# CapTouchKeyboard_v2_0.net
KiCad netlist of a schematic drawn in Altium Designer
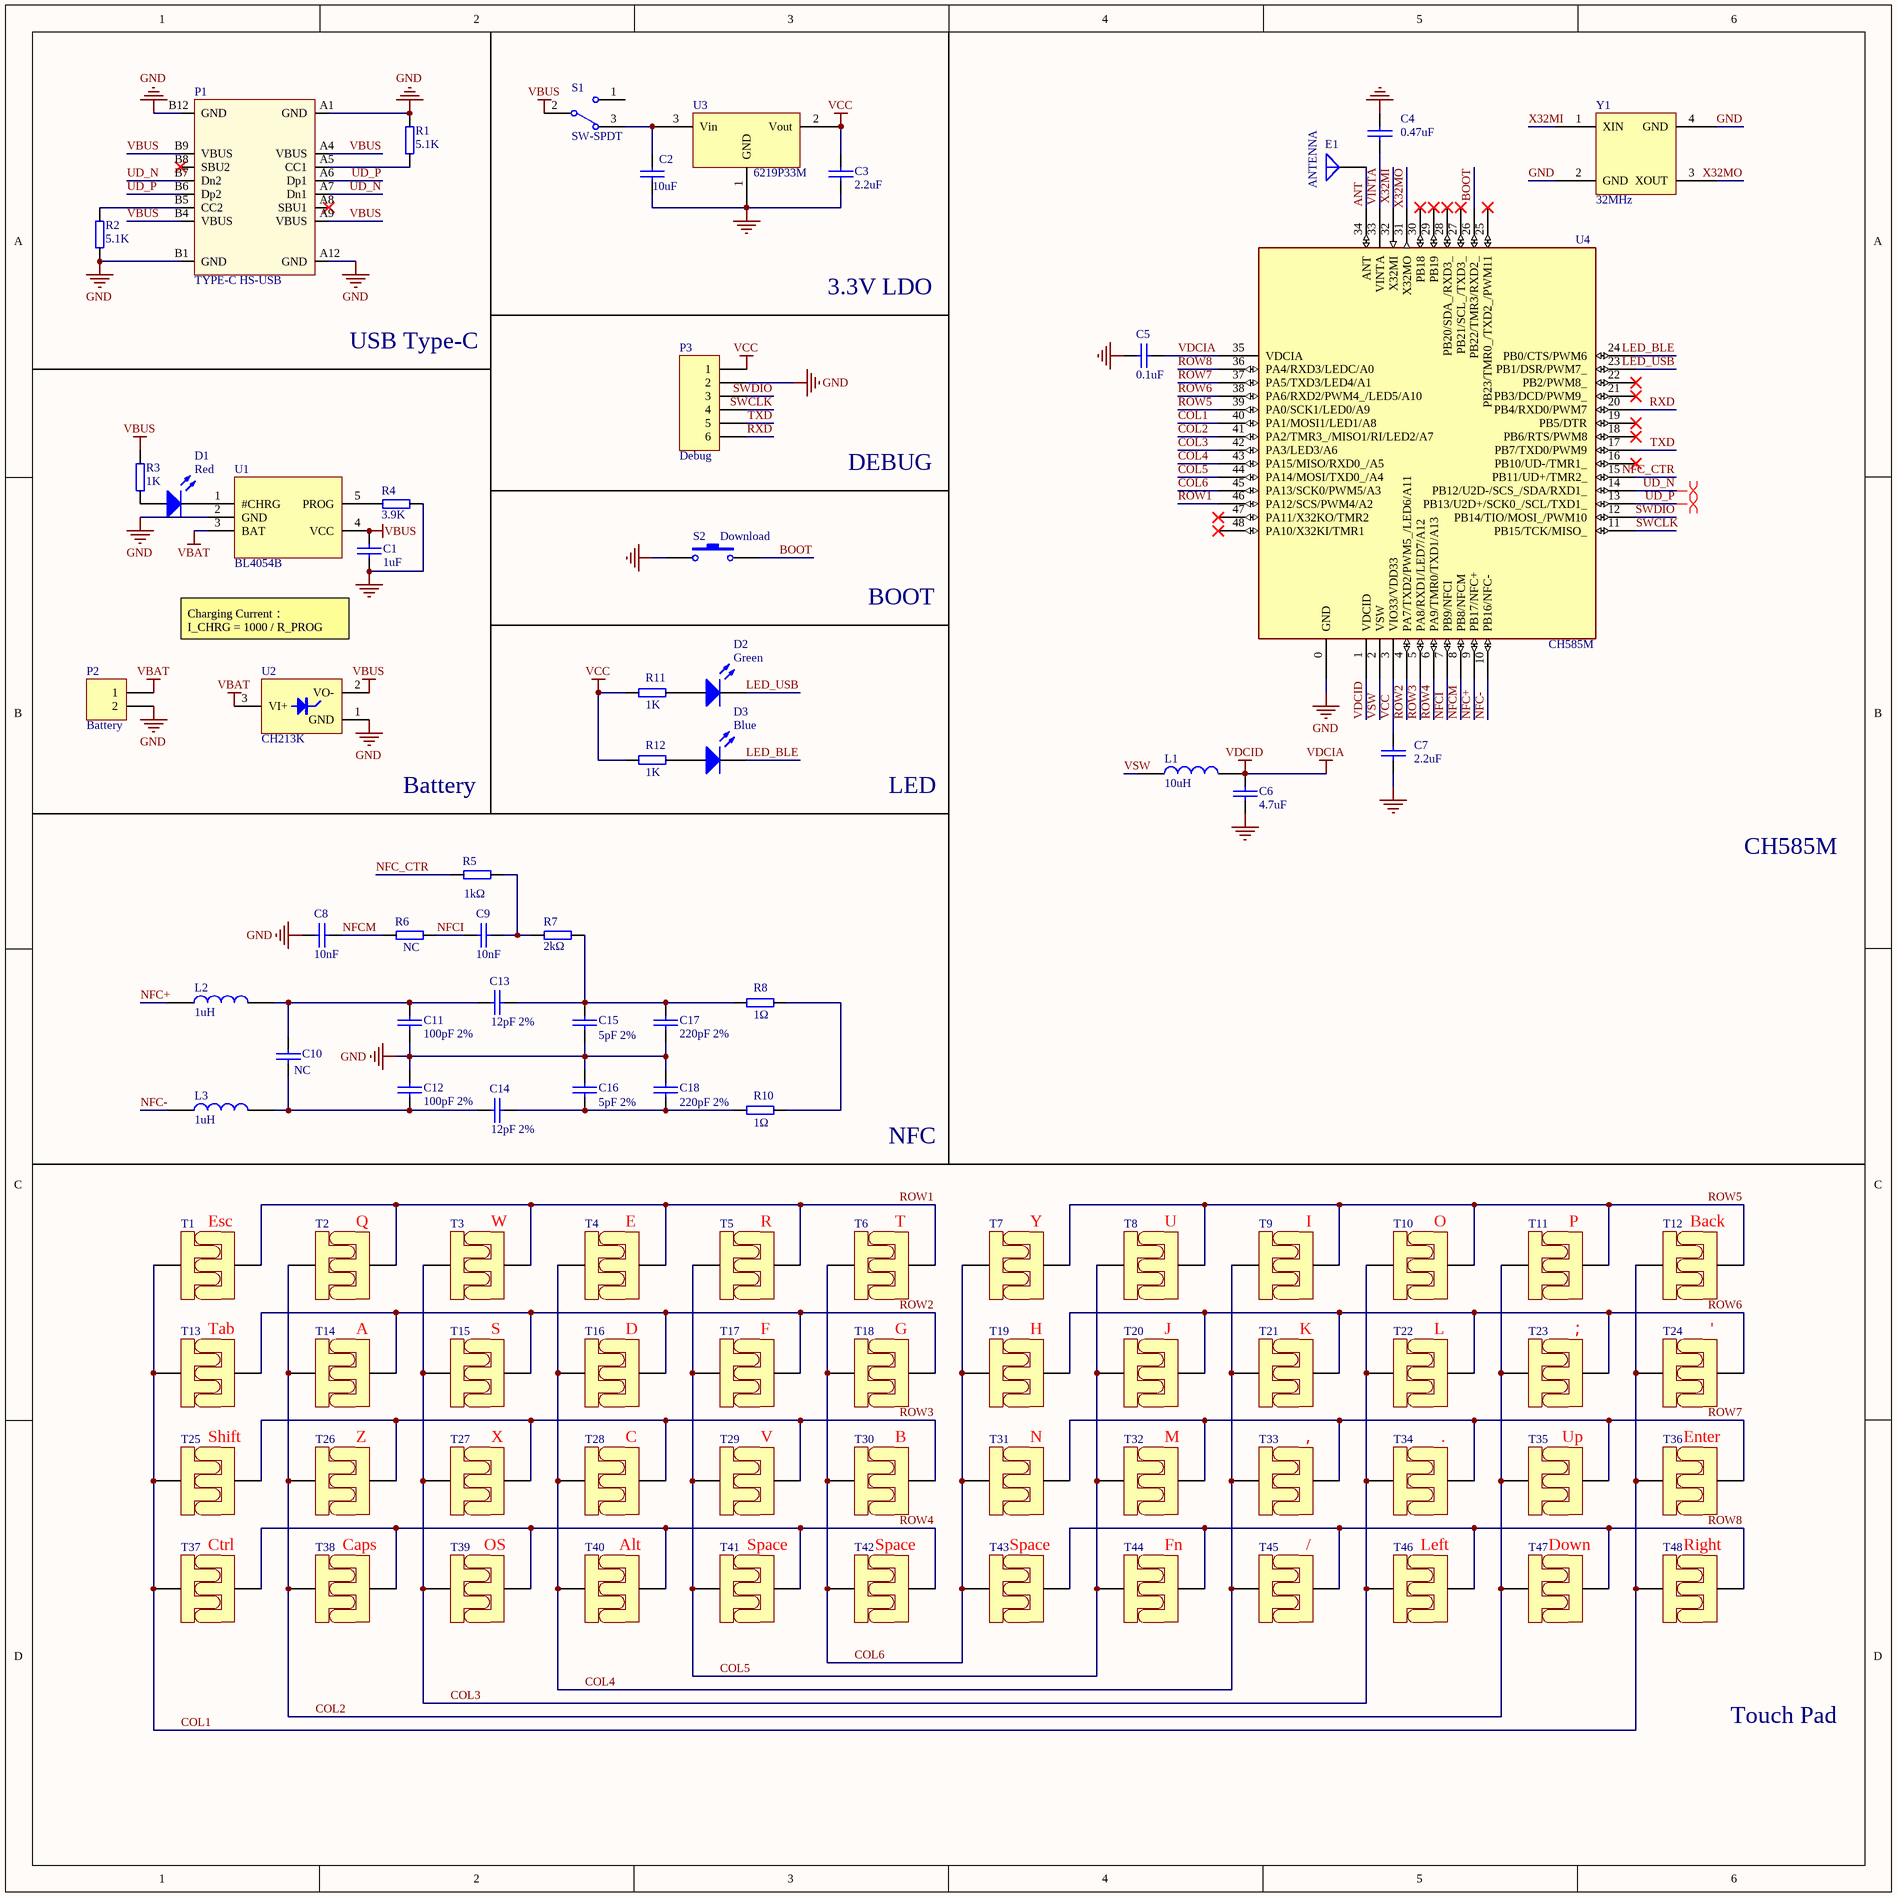
[diagram p0: CapTouchKeyboard_v2.0.SchDoc]

(export (version "E")
  (design (tool "Eeschema 10.0.6"))
  (components
    (comp (ref "C1")
      (value "1uF")
      (footprint "CapTouchKeyboard:0402_C")
      (description "Capacitor")
      (libsource (lib "*") (part "CAP"))
    )
    (comp (ref "C2")
      (value "10uF")
      (footprint "CapTouchKeyboard:0603_C")
      (description "Capacitor")
      (libsource (lib "*") (part "CAP"))
    )
    (comp (ref "C3")
      (value "2.2uF")
      (footprint "CapTouchKeyboard:0402_C")
      (description "Capacitor")
      (libsource (lib "*") (part "CAP"))
    )
    (comp (ref "C4")
      (value "0.47uF")
      (footprint "CapTouchKeyboard:0402_C")
      (description "Capacitor")
      (libsource (lib "*") (part "CAP"))
    )
    (comp (ref "C5")
      (value "0.1uF")
      (footprint "CapTouchKeyboard:0402_C")
      (description "Capacitor")
      (libsource (lib "*") (part "CAP"))
    )
    (comp (ref "C6")
      (value "4.7uF")
      (footprint "CapTouchKeyboard:0402_C")
      (description "Capacitor")
      (libsource (lib "") (part "CAP_1"))
    )
    (comp (ref "C7")
      (value "2.2uF")
      (footprint "CapTouchKeyboard:0402_C")
      (description "Capacitor")
      (libsource (lib "*") (part "CAP"))
    )
    (comp (ref "C8")
      (value "10nF")
      (footprint "CapTouchKeyboard:0402_C")
      (description "Capacitor")
      (libsource (lib "wch_sch_others") (part "CAP"))
    )
    (comp (ref "C9")
      (value "10nF")
      (footprint "CapTouchKeyboard:0402_C")
      (description "Capacitor")
      (libsource (lib "wch_sch_others") (part "CAP"))
    )
    (comp (ref "C10")
      (value "NC")
      (footprint "CapTouchKeyboard:0402_C")
      (description "Capacitor")
      (libsource (lib "wch_sch_others") (part "CAP"))
    )
    (comp (ref "C11")
      (value "100pF 2%")
      (footprint "CapTouchKeyboard:0402_C")
      (description "Capacitor")
      (libsource (lib "wch_sch_others") (part "CAP"))
    )
    (comp (ref "C12")
      (value "100pF 2%")
      (footprint "CapTouchKeyboard:0402_C")
      (description "Capacitor")
      (libsource (lib "wch_sch_others") (part "CAP"))
    )
    (comp (ref "C13")
      (value "12pF 2%")
      (footprint "CapTouchKeyboard:0402_C")
      (description "Capacitor")
      (libsource (lib "wch_sch_others") (part "CAP"))
    )
    (comp (ref "C14")
      (value "12pF 2%")
      (footprint "CapTouchKeyboard:0402_C")
      (description "Capacitor")
      (libsource (lib "wch_sch_others") (part "CAP"))
    )
    (comp (ref "C15")
      (value "5pF 2%")
      (footprint "CapTouchKeyboard:0402_C")
      (description "Capacitor")
      (libsource (lib "wch_sch_others") (part "CAP"))
    )
    (comp (ref "C16")
      (value "5pF 2%")
      (footprint "CapTouchKeyboard:0402_C")
      (description "Capacitor")
      (libsource (lib "wch_sch_others") (part "CAP"))
    )
    (comp (ref "C17")
      (value "220pF 2%")
      (footprint "CapTouchKeyboard:0402_C")
      (description "Capacitor")
      (libsource (lib "wch_sch_others") (part "CAP"))
    )
    (comp (ref "C18")
      (value "220pF 2%")
      (footprint "CapTouchKeyboard:0402_C")
      (description "Capacitor")
      (libsource (lib "wch_sch_others") (part "CAP"))
    )
    (comp (ref "D1")
      (value "Red")
      (footprint "ADLIB:0603+")
      (description "Typical INFRARED GaAs LED")
      (fields (field (name "PUBLISHER") "Altium Limited"))
      (libsource (lib "Miscellaneous Devices") (part "LED0"))
    )
    (comp (ref "D2")
      (value "Green")
      (footprint "ADLIB:0603+")
      (description "Typical INFRARED GaAs LED")
      (fields (field (name "PUBLISHER") "Altium Limited"))
      (libsource (lib "Miscellaneous Devices") (part "LED0"))
    )
    (comp (ref "D3")
      (value "Blue")
      (footprint "ADLIB:0603+")
      (description "Typical INFRARED GaAs LED")
      (fields (field (name "PUBLISHER") "Altium Limited"))
      (libsource (lib "Miscellaneous Devices") (part "LED0"))
    )
    (comp (ref "E1")
      (value "ANTENNA")
      (footprint "CapTouchKeyboard:ANT-F-1-2.4G-0.8mmFR4-WCH")
      (description "Generic Antenna")
      (libsource (lib "*") (part "ANTENNA"))
    )
    (comp (ref "L1")
      (value "10uH")
      (footprint "CapTouchKeyboard:SMD_2x2mm")
      (libsource (lib "*") (part "INDUCTOR"))
    )
    (comp (ref "L2") (value "1uH") (footprint "CHXXX:0603") (libsource (lib "*") (part "INDUCTOR")))
    (comp (ref "L3") (value "1uH") (footprint "CHXXX:0603") (libsource (lib "*") (part "INDUCTOR")))
    (comp (ref "P1")
      (value "TYPE-C HS-USB")
      (footprint "USB_TYPE_C_DS_2")
      (description "Type-C USB2.0 母座")
      (libsource (lib "CapTouchKeyboard") (part "TYPE-C-Receptacle-2.0"))
    )
    (comp (ref "P2")
      (value "Battery")
      (footprint "CapTouchKeyboard:XH-2P-P1.25mm-WT")
      (description "Header, 2-Pin")
      (libsource (lib "wch_sch_others") (part "HEADER 2"))
    )
    (comp (ref "P3")
      (value "Debug")
      (footprint "CapTouchKeyboard:HDR1X6H")
      (description "Header, 6-Pin")
      (libsource (lib "CapTouchKeyboard") (part "HEADER 6"))
    )
    (comp (ref "R1") (value "5.1K") (footprint "CHXXX:0402") (libsource (lib "wch_sch_others") (part "RES")))
    (comp (ref "R2") (value "5.1K") (footprint "CHXXX:0402") (libsource (lib "wch_sch_others") (part "RES")))
    (comp (ref "R3") (value "1K") (footprint "CHXXX:0402") (libsource (lib "wch_sch_others") (part "RES")))
    (comp (ref "R4") (value "3.9K") (footprint "CHXXX:0402") (libsource (lib "wch_sch_others") (part "RES")))
    (comp (ref "R5") (value "1kΩ") (footprint "CHXXX:0402") (libsource (lib "wch_sch_others") (part "RES")))
    (comp (ref "R6") (value "NC") (footprint "CHXXX:0402") (libsource (lib "wch_sch_others") (part "RES")))
    (comp (ref "R7") (value "2kΩ") (footprint "CHXXX:0402") (libsource (lib "wch_sch_others") (part "RES")))
    (comp (ref "R8") (value "1Ω") (footprint "CHXXX:0402") (libsource (lib "wch_sch_others") (part "RES")))
    (comp (ref "R10") (value "1Ω") (footprint "CHXXX:0402") (libsource (lib "wch_sch_others") (part "RES")))
    (comp (ref "R11") (value "1K") (footprint "CHXXX:0402") (libsource (lib "wch_sch_others") (part "RES")))
    (comp (ref "R12") (value "1K") (footprint "CHXXX:0402") (libsource (lib "wch_sch_others") (part "RES")))
    (comp (ref "S1")
      (value "SW-SPDT")
      (footprint "CapTouchKeyboard:SW1 - SMD (2)")
      (description "SPDT Subminiature Toggle Switch, Right Angle Mounting, Vertical Actuation")
      (fields (field (name "PUBLISHER") "Altium Limited"))
      (libsource (lib "Miscellaneous Devices") (part "SW-SPDT"))
    )
    (comp (ref "S2")
      (value "Download")
      (footprint "CapTouchKeyboard:SMD_4.1x2.3x3.5mm-KEY (2)")
      (description "Switch")
      (fields (field (name "PUBLISHER") "Altium Limited"))
      (libsource (lib "CapTouchKeyboard") (part "SW-PB"))
    )
    (comp (ref "T1")
      (value "TouchPad")
      (footprint "CapTouchKeyboard:TOUCH_PAD")
      (libsource (lib "CapTouchKeyboard") (part "TouchPad"))
    )
    (comp (ref "T2")
      (value "TouchPad")
      (footprint "CapTouchKeyboard:TOUCH_PAD")
      (libsource (lib "CapTouchKeyboard") (part "TouchPad"))
    )
    (comp (ref "T3")
      (value "TouchPad")
      (footprint "CapTouchKeyboard:TOUCH_PAD")
      (libsource (lib "CapTouchKeyboard") (part "TouchPad"))
    )
    (comp (ref "T4")
      (value "TouchPad")
      (footprint "CapTouchKeyboard:TOUCH_PAD")
      (libsource (lib "CapTouchKeyboard") (part "TouchPad"))
    )
    (comp (ref "T5")
      (value "TouchPad")
      (footprint "CapTouchKeyboard:TOUCH_PAD")
      (libsource (lib "CapTouchKeyboard") (part "TouchPad"))
    )
    (comp (ref "T6")
      (value "TouchPad")
      (footprint "CapTouchKeyboard:TOUCH_PAD")
      (libsource (lib "CapTouchKeyboard") (part "TouchPad"))
    )
    (comp (ref "T7")
      (value "TouchPad")
      (footprint "CapTouchKeyboard:TOUCH_PAD")
      (libsource (lib "CapTouchKeyboard") (part "TouchPad"))
    )
    (comp (ref "T8")
      (value "TouchPad")
      (footprint "CapTouchKeyboard:TOUCH_PAD")
      (libsource (lib "CapTouchKeyboard") (part "TouchPad"))
    )
    (comp (ref "T9")
      (value "TouchPad")
      (footprint "CapTouchKeyboard:TOUCH_PAD")
      (libsource (lib "CapTouchKeyboard") (part "TouchPad"))
    )
    (comp (ref "T10")
      (value "TouchPad")
      (footprint "CapTouchKeyboard:TOUCH_PAD")
      (libsource (lib "CapTouchKeyboard") (part "TouchPad"))
    )
    (comp (ref "T11")
      (value "TouchPad")
      (footprint "CapTouchKeyboard:TOUCH_PAD")
      (libsource (lib "CapTouchKeyboard") (part "TouchPad"))
    )
    (comp (ref "T12")
      (value "TouchPad")
      (footprint "CapTouchKeyboard:TOUCH_PAD")
      (libsource (lib "CapTouchKeyboard") (part "TouchPad"))
    )
    (comp (ref "T13")
      (value "TouchPad")
      (footprint "CapTouchKeyboard:TOUCH_PAD")
      (libsource (lib "CapTouchKeyboard") (part "TouchPad"))
    )
    (comp (ref "T14")
      (value "TouchPad")
      (footprint "CapTouchKeyboard:TOUCH_PAD")
      (libsource (lib "CapTouchKeyboard") (part "TouchPad"))
    )
    (comp (ref "T15")
      (value "TouchPad")
      (footprint "CapTouchKeyboard:TOUCH_PAD")
      (libsource (lib "CapTouchKeyboard") (part "TouchPad"))
    )
    (comp (ref "T16")
      (value "TouchPad")
      (footprint "CapTouchKeyboard:TOUCH_PAD")
      (libsource (lib "CapTouchKeyboard") (part "TouchPad"))
    )
    (comp (ref "T17")
      (value "TouchPad")
      (footprint "CapTouchKeyboard:TOUCH_PAD")
      (libsource (lib "CapTouchKeyboard") (part "TouchPad"))
    )
    (comp (ref "T18")
      (value "TouchPad")
      (footprint "CapTouchKeyboard:TOUCH_PAD")
      (libsource (lib "CapTouchKeyboard") (part "TouchPad"))
    )
    (comp (ref "T19")
      (value "TouchPad")
      (footprint "CapTouchKeyboard:TOUCH_PAD")
      (libsource (lib "CapTouchKeyboard") (part "TouchPad"))
    )
    (comp (ref "T20")
      (value "TouchPad")
      (footprint "CapTouchKeyboard:TOUCH_PAD")
      (libsource (lib "CapTouchKeyboard") (part "TouchPad"))
    )
    (comp (ref "T21")
      (value "TouchPad")
      (footprint "CapTouchKeyboard:TOUCH_PAD")
      (libsource (lib "CapTouchKeyboard") (part "TouchPad"))
    )
    (comp (ref "T22")
      (value "TouchPad")
      (footprint "CapTouchKeyboard:TOUCH_PAD")
      (libsource (lib "CapTouchKeyboard") (part "TouchPad"))
    )
    (comp (ref "T23")
      (value "TouchPad")
      (footprint "CapTouchKeyboard:TOUCH_PAD")
      (libsource (lib "CapTouchKeyboard") (part "TouchPad"))
    )
    (comp (ref "T24")
      (value "TouchPad")
      (footprint "CapTouchKeyboard:TOUCH_PAD")
      (libsource (lib "CapTouchKeyboard") (part "TouchPad"))
    )
    (comp (ref "T25")
      (value "TouchPad")
      (footprint "CapTouchKeyboard:TOUCH_PAD")
      (libsource (lib "CapTouchKeyboard") (part "TouchPad"))
    )
    (comp (ref "T26")
      (value "TouchPad")
      (footprint "CapTouchKeyboard:TOUCH_PAD")
      (libsource (lib "CapTouchKeyboard") (part "TouchPad"))
    )
    (comp (ref "T27")
      (value "TouchPad")
      (footprint "CapTouchKeyboard:TOUCH_PAD")
      (libsource (lib "CapTouchKeyboard") (part "TouchPad"))
    )
    (comp (ref "T28")
      (value "TouchPad")
      (footprint "CapTouchKeyboard:TOUCH_PAD")
      (libsource (lib "CapTouchKeyboard") (part "TouchPad"))
    )
    (comp (ref "T29")
      (value "TouchPad")
      (footprint "CapTouchKeyboard:TOUCH_PAD")
      (libsource (lib "CapTouchKeyboard") (part "TouchPad"))
    )
    (comp (ref "T30")
      (value "TouchPad")
      (footprint "CapTouchKeyboard:TOUCH_PAD")
      (libsource (lib "CapTouchKeyboard") (part "TouchPad"))
    )
    (comp (ref "T31")
      (value "TouchPad")
      (footprint "CapTouchKeyboard:TOUCH_PAD")
      (libsource (lib "CapTouchKeyboard") (part "TouchPad"))
    )
    (comp (ref "T32")
      (value "TouchPad")
      (footprint "CapTouchKeyboard:TOUCH_PAD")
      (libsource (lib "CapTouchKeyboard") (part "TouchPad"))
    )
    (comp (ref "T33")
      (value "TouchPad")
      (footprint "CapTouchKeyboard:TOUCH_PAD")
      (libsource (lib "CapTouchKeyboard") (part "TouchPad"))
    )
    (comp (ref "T34")
      (value "TouchPad")
      (footprint "CapTouchKeyboard:TOUCH_PAD")
      (libsource (lib "CapTouchKeyboard") (part "TouchPad"))
    )
    (comp (ref "T35")
      (value "TouchPad")
      (footprint "CapTouchKeyboard:TOUCH_PAD")
      (libsource (lib "CapTouchKeyboard") (part "TouchPad"))
    )
    (comp (ref "T36")
      (value "TouchPad")
      (footprint "CapTouchKeyboard:TOUCH_PAD")
      (libsource (lib "CapTouchKeyboard") (part "TouchPad"))
    )
    (comp (ref "T37")
      (value "TouchPad")
      (footprint "CapTouchKeyboard:TOUCH_PAD")
      (libsource (lib "CapTouchKeyboard") (part "TouchPad"))
    )
    (comp (ref "T38")
      (value "TouchPad")
      (footprint "CapTouchKeyboard:TOUCH_PAD")
      (libsource (lib "CapTouchKeyboard") (part "TouchPad"))
    )
    (comp (ref "T39")
      (value "TouchPad")
      (footprint "CapTouchKeyboard:TOUCH_PAD")
      (libsource (lib "CapTouchKeyboard") (part "TouchPad"))
    )
    (comp (ref "T40")
      (value "TouchPad")
      (footprint "CapTouchKeyboard:TOUCH_PAD")
      (libsource (lib "CapTouchKeyboard") (part "TouchPad"))
    )
    (comp (ref "T41")
      (value "TouchPad")
      (footprint "CapTouchKeyboard:TOUCH_PAD")
      (libsource (lib "CapTouchKeyboard") (part "TouchPad"))
    )
    (comp (ref "T42")
      (value "TouchPad")
      (footprint "CapTouchKeyboard:TOUCH_PAD")
      (libsource (lib "CapTouchKeyboard") (part "TouchPad"))
    )
    (comp (ref "T43")
      (value "TouchPad")
      (footprint "CapTouchKeyboard:TOUCH_PAD")
      (libsource (lib "CapTouchKeyboard") (part "TouchPad"))
    )
    (comp (ref "T44")
      (value "TouchPad")
      (footprint "CapTouchKeyboard:TOUCH_PAD")
      (libsource (lib "CapTouchKeyboard") (part "TouchPad"))
    )
    (comp (ref "T45")
      (value "TouchPad")
      (footprint "CapTouchKeyboard:TOUCH_PAD")
      (libsource (lib "CapTouchKeyboard") (part "TouchPad"))
    )
    (comp (ref "T46")
      (value "TouchPad")
      (footprint "CapTouchKeyboard:TOUCH_PAD")
      (libsource (lib "CapTouchKeyboard") (part "TouchPad"))
    )
    (comp (ref "T47")
      (value "TouchPad")
      (footprint "CapTouchKeyboard:TOUCH_PAD")
      (libsource (lib "CapTouchKeyboard") (part "TouchPad"))
    )
    (comp (ref "T48")
      (value "TouchPad")
      (footprint "CapTouchKeyboard:TOUCH_PAD")
      (libsource (lib "CapTouchKeyboard") (part "TouchPad"))
    )
    (comp (ref "U1")
      (value "BL4054B")
      (footprint "CHXXX:SOT-23-5")
      (description "具有热调节功能的800mA独立线性锂离子电池充电器")
      (libsource (lib "CapTouchKeyboard") (part "BL4054B"))
    )
    (comp (ref "U2")
      (value "CH213K")
      (footprint "CHXXX:SOT-23-3")
      (description "Ideal Diode 5V*1A")
      (libsource (lib "DHXXXSCH") (part "CH213K"))
    )
    (comp (ref "U3")
      (value "6219P33M")
      (footprint "CHXXX:SOT-23")
      (libsource (lib "wch_sch_others") (part "6219P33M"))
    )
    (comp (ref "U4")
      (value "CH585M")
      (footprint "QFN48_5X5")
      (description "RISC-V MCU with BLE/HSUSB/USB/NFC/ADC/PWM/2*SPI/I2C/4*UART/LCD")
      (libsource (lib "CapTouchKeyboard") (part "CH585M"))
    )
    (comp (ref "Y1")
      (value "32MHz")
      (footprint "CapTouchKeyboard:2016")
      (libsource (lib "wch_sch_others") (part "晶体"))
    )
  )
  (nets
    (net (code "1") (name "/ANT") (class "Default")
      (node (ref "E1") (pin "1") (pinfunction "A_1") (pintype "passive"))
      (node (ref "U4") (pin "34") (pinfunction "ANT_34") (pintype "bidirectional"))
    )
    (net (code "2") (name "/BOOT") (class "Default")
      (node (ref "S2") (pin "2") (pinfunction "2_2") (pintype "passive"))
      (node (ref "U4") (pin "26") (pinfunction "PB22/TMR3/RXD2__26") (pintype "bidirectional"))
    )
    (net (code "3") (name "/COL1") (class "Default")
      (node (ref "T1") (pin "1") (pinfunction "1_1") (pintype "passive"))
      (node (ref "T12") (pin "1") (pinfunction "1_1") (pintype "passive"))
      (node (ref "T13") (pin "1") (pinfunction "1_1") (pintype "passive"))
      (node (ref "T24") (pin "1") (pinfunction "1_1") (pintype "passive"))
      (node (ref "T25") (pin "1") (pinfunction "1_1") (pintype "passive"))
      (node (ref "T36") (pin "1") (pinfunction "1_1") (pintype "passive"))
      (node (ref "T37") (pin "1") (pinfunction "1_1") (pintype "passive"))
      (node (ref "T48") (pin "1") (pinfunction "1_1") (pintype "passive"))
      (node (ref "U4") (pin "40") (pinfunction "PA1/MOSI1/LED1/A8_40") (pintype "bidirectional"))
    )
    (net (code "4") (name "/COL2") (class "Default")
      (node (ref "T11") (pin "1") (pinfunction "1_1") (pintype "passive"))
      (node (ref "T14") (pin "1") (pinfunction "1_1") (pintype "passive"))
      (node (ref "T2") (pin "1") (pinfunction "1_1") (pintype "passive"))
      (node (ref "T23") (pin "1") (pinfunction "1_1") (pintype "passive"))
      (node (ref "T26") (pin "1") (pinfunction "1_1") (pintype "passive"))
      (node (ref "T35") (pin "1") (pinfunction "1_1") (pintype "passive"))
      (node (ref "T38") (pin "1") (pinfunction "1_1") (pintype "passive"))
      (node (ref "T47") (pin "1") (pinfunction "1_1") (pintype "passive"))
      (node (ref "U4") (pin "41") (pinfunction "PA2/TMR3_/MISO1/RI/LED2/A7_41") (pintype "bidirectional"))
    )
    (net (code "5") (name "/COL3") (class "Default")
      (node (ref "T10") (pin "1") (pinfunction "1_1") (pintype "passive"))
      (node (ref "T15") (pin "1") (pinfunction "1_1") (pintype "passive"))
      (node (ref "T22") (pin "1") (pinfunction "1_1") (pintype "passive"))
      (node (ref "T27") (pin "1") (pinfunction "1_1") (pintype "passive"))
      (node (ref "T3") (pin "1") (pinfunction "1_1") (pintype "passive"))
      (node (ref "T34") (pin "1") (pinfunction "1_1") (pintype "passive"))
      (node (ref "T39") (pin "1") (pinfunction "1_1") (pintype "passive"))
      (node (ref "T46") (pin "1") (pinfunction "1_1") (pintype "passive"))
      (node (ref "U4") (pin "42") (pinfunction "PA3/LED3/A6_42") (pintype "bidirectional"))
    )
    (net (code "6") (name "/COL4") (class "Default")
      (node (ref "T16") (pin "1") (pinfunction "1_1") (pintype "passive"))
      (node (ref "T21") (pin "1") (pinfunction "1_1") (pintype "passive"))
      (node (ref "T28") (pin "1") (pinfunction "1_1") (pintype "passive"))
      (node (ref "T33") (pin "1") (pinfunction "1_1") (pintype "passive"))
      (node (ref "T4") (pin "1") (pinfunction "1_1") (pintype "passive"))
      (node (ref "T40") (pin "1") (pinfunction "1_1") (pintype "passive"))
      (node (ref "T45") (pin "1") (pinfunction "1_1") (pintype "passive"))
      (node (ref "T9") (pin "1") (pinfunction "1_1") (pintype "passive"))
      (node (ref "U4") (pin "43") (pinfunction "PA15/MISO/RXD0_/A5_43") (pintype "bidirectional"))
    )
    (net (code "7") (name "/COL5") (class "Default")
      (node (ref "T17") (pin "1") (pinfunction "1_1") (pintype "passive"))
      (node (ref "T20") (pin "1") (pinfunction "1_1") (pintype "passive"))
      (node (ref "T29") (pin "1") (pinfunction "1_1") (pintype "passive"))
      (node (ref "T32") (pin "1") (pinfunction "1_1") (pintype "passive"))
      (node (ref "T41") (pin "1") (pinfunction "1_1") (pintype "passive"))
      (node (ref "T44") (pin "1") (pinfunction "1_1") (pintype "passive"))
      (node (ref "T5") (pin "1") (pinfunction "1_1") (pintype "passive"))
      (node (ref "T8") (pin "1") (pinfunction "1_1") (pintype "passive"))
      (node (ref "U4") (pin "44") (pinfunction "PA14/MOSI/TXD0_/A4_44") (pintype "bidirectional"))
    )
    (net (code "8") (name "/COL6") (class "Default")
      (node (ref "T18") (pin "1") (pinfunction "1_1") (pintype "passive"))
      (node (ref "T19") (pin "1") (pinfunction "1_1") (pintype "passive"))
      (node (ref "T30") (pin "1") (pinfunction "1_1") (pintype "passive"))
      (node (ref "T31") (pin "1") (pinfunction "1_1") (pintype "passive"))
      (node (ref "T42") (pin "1") (pinfunction "1_1") (pintype "passive"))
      (node (ref "T43") (pin "1") (pinfunction "1_1") (pintype "passive"))
      (node (ref "T6") (pin "1") (pinfunction "1_1") (pintype "passive"))
      (node (ref "T7") (pin "1") (pinfunction "1_1") (pintype "passive"))
      (node (ref "U4") (pin "45") (pinfunction "PA13/SCK0/PWM5/A3_45") (pintype "bidirectional"))
    )
    (net (code "9") (name "/LED_BLE") (class "Default")
      (node (ref "D3") (pin "2") (pinfunction "K_2") (pintype "passive"))
      (node (ref "U4") (pin "24") (pinfunction "PB0/CTS/PWM6_24") (pintype "bidirectional"))
    )
    (net (code "10") (name "/LED_USB") (class "Default")
      (node (ref "D2") (pin "2") (pinfunction "K_2") (pintype "passive"))
      (node (ref "U4") (pin "23") (pinfunction "PB1/DSR/PWM7__23") (pintype "bidirectional"))
    )
    (net (code "11") (name "/NFC+") (class "Default")
      (node (ref "L2") (pin "1") (pinfunction "1_1") (pintype "passive"))
      (node (ref "U4") (pin "9") (pinfunction "PB17/NFC+_9") (pintype "bidirectional"))
    )
    (net (code "12") (name "/NFC-") (class "Default")
      (node (ref "L3") (pin "1") (pinfunction "1_1") (pintype "passive"))
      (node (ref "U4") (pin "10") (pinfunction "PB16/NFC-_10") (pintype "bidirectional"))
    )
    (net (code "13") (name "/NFCI") (class "Default")
      (node (ref "C9") (pin "1") (pinfunction "1_1") (pintype "passive"))
      (node (ref "R6") (pin "1") (pintype "passive"))
      (node (ref "U4") (pin "7") (pinfunction "PB9/NFCI_7") (pintype "bidirectional"))
    )
    (net (code "14") (name "/NFCM") (class "Default")
      (node (ref "C8") (pin "1") (pinfunction "1_1") (pintype "passive"))
      (node (ref "R6") (pin "2") (pintype "passive"))
      (node (ref "U4") (pin "8") (pinfunction "PB8/NFCM_8") (pintype "bidirectional"))
    )
    (net (code "15") (name "/NFC_CTR") (class "Default")
      (node (ref "R5") (pin "2") (pintype "passive"))
      (node (ref "U4") (pin "15") (pinfunction "PB11/UD+/TMR2__15") (pintype "bidirectional"))
    )
    (net (code "16") (name "/ROW1") (class "Default")
      (node (ref "T1") (pin "2") (pinfunction "2_2") (pintype "passive"))
      (node (ref "T2") (pin "2") (pinfunction "2_2") (pintype "passive"))
      (node (ref "T3") (pin "2") (pinfunction "2_2") (pintype "passive"))
      (node (ref "T4") (pin "2") (pinfunction "2_2") (pintype "passive"))
      (node (ref "T5") (pin "2") (pinfunction "2_2") (pintype "passive"))
      (node (ref "T6") (pin "2") (pinfunction "2_2") (pintype "passive"))
      (node (ref "U4") (pin "46") (pinfunction "PA12/SCS/PWM4/A2_46") (pintype "bidirectional"))
    )
    (net (code "17") (name "/ROW2") (class "Default")
      (node (ref "T13") (pin "2") (pinfunction "2_2") (pintype "passive"))
      (node (ref "T14") (pin "2") (pinfunction "2_2") (pintype "passive"))
      (node (ref "T15") (pin "2") (pinfunction "2_2") (pintype "passive"))
      (node (ref "T16") (pin "2") (pinfunction "2_2") (pintype "passive"))
      (node (ref "T17") (pin "2") (pinfunction "2_2") (pintype "passive"))
      (node (ref "T18") (pin "2") (pinfunction "2_2") (pintype "passive"))
      (node (ref "U4") (pin "4") (pinfunction "PA7/TXD2/PWM5_/LED6/A11_4") (pintype "bidirectional"))
    )
    (net (code "18") (name "/ROW3") (class "Default")
      (node (ref "T25") (pin "2") (pinfunction "2_2") (pintype "passive"))
      (node (ref "T26") (pin "2") (pinfunction "2_2") (pintype "passive"))
      (node (ref "T27") (pin "2") (pinfunction "2_2") (pintype "passive"))
      (node (ref "T28") (pin "2") (pinfunction "2_2") (pintype "passive"))
      (node (ref "T29") (pin "2") (pinfunction "2_2") (pintype "passive"))
      (node (ref "T30") (pin "2") (pinfunction "2_2") (pintype "passive"))
      (node (ref "U4") (pin "5") (pinfunction "PA8/RXD1/LED7/A12_5") (pintype "bidirectional"))
    )
    (net (code "19") (name "/ROW4") (class "Default")
      (node (ref "T37") (pin "2") (pinfunction "2_2") (pintype "passive"))
      (node (ref "T38") (pin "2") (pinfunction "2_2") (pintype "passive"))
      (node (ref "T39") (pin "2") (pinfunction "2_2") (pintype "passive"))
      (node (ref "T40") (pin "2") (pinfunction "2_2") (pintype "passive"))
      (node (ref "T41") (pin "2") (pinfunction "2_2") (pintype "passive"))
      (node (ref "T42") (pin "2") (pinfunction "2_2") (pintype "passive"))
      (node (ref "U4") (pin "6") (pinfunction "PA9/TMR0/TXD1/A13_6") (pintype "bidirectional"))
    )
    (net (code "20") (name "/ROW5") (class "Default")
      (node (ref "T10") (pin "2") (pinfunction "2_2") (pintype "passive"))
      (node (ref "T11") (pin "2") (pinfunction "2_2") (pintype "passive"))
      (node (ref "T12") (pin "2") (pinfunction "2_2") (pintype "passive"))
      (node (ref "T7") (pin "2") (pinfunction "2_2") (pintype "passive"))
      (node (ref "T8") (pin "2") (pinfunction "2_2") (pintype "passive"))
      (node (ref "T9") (pin "2") (pinfunction "2_2") (pintype "passive"))
      (node (ref "U4") (pin "39") (pinfunction "PA0/SCK1/LED0/A9_39") (pintype "bidirectional"))
    )
    (net (code "21") (name "/ROW6") (class "Default")
      (node (ref "T19") (pin "2") (pinfunction "2_2") (pintype "passive"))
      (node (ref "T20") (pin "2") (pinfunction "2_2") (pintype "passive"))
      (node (ref "T21") (pin "2") (pinfunction "2_2") (pintype "passive"))
      (node (ref "T22") (pin "2") (pinfunction "2_2") (pintype "passive"))
      (node (ref "T23") (pin "2") (pinfunction "2_2") (pintype "passive"))
      (node (ref "T24") (pin "2") (pinfunction "2_2") (pintype "passive"))
      (node (ref "U4") (pin "38") (pinfunction "PA6/RXD2/PWM4_/LED5/A10_38") (pintype "bidirectional"))
    )
    (net (code "22") (name "/ROW7") (class "Default")
      (node (ref "T31") (pin "2") (pinfunction "2_2") (pintype "passive"))
      (node (ref "T32") (pin "2") (pinfunction "2_2") (pintype "passive"))
      (node (ref "T33") (pin "2") (pinfunction "2_2") (pintype "passive"))
      (node (ref "T34") (pin "2") (pinfunction "2_2") (pintype "passive"))
      (node (ref "T35") (pin "2") (pinfunction "2_2") (pintype "passive"))
      (node (ref "T36") (pin "2") (pinfunction "2_2") (pintype "passive"))
      (node (ref "U4") (pin "37") (pinfunction "PA5/TXD3/LED4/A1_37") (pintype "bidirectional"))
    )
    (net (code "23") (name "/ROW8") (class "Default")
      (node (ref "T43") (pin "2") (pinfunction "2_2") (pintype "passive"))
      (node (ref "T44") (pin "2") (pinfunction "2_2") (pintype "passive"))
      (node (ref "T45") (pin "2") (pinfunction "2_2") (pintype "passive"))
      (node (ref "T46") (pin "2") (pinfunction "2_2") (pintype "passive"))
      (node (ref "T47") (pin "2") (pinfunction "2_2") (pintype "passive"))
      (node (ref "T48") (pin "2") (pinfunction "2_2") (pintype "passive"))
      (node (ref "U4") (pin "36") (pinfunction "PA4/RXD3/LEDC/A0_36") (pintype "bidirectional"))
    )
    (net (code "24") (name "/RXD") (class "Default")
      (node (ref "P3") (pin "6") (pinfunction "6_6") (pintype "passive"))
      (node (ref "U4") (pin "20") (pinfunction "PB4/RXD0/PWM7_20") (pintype "bidirectional"))
    )
    (net (code "25") (name "/SWCLK") (class "Default")
      (node (ref "P3") (pin "4") (pinfunction "4_4") (pintype "passive"))
      (node (ref "U4") (pin "11") (pinfunction "PB15/TCK/MISO__11") (pintype "bidirectional"))
    )
    (net (code "26") (name "/SWDIO") (class "Default")
      (node (ref "P3") (pin "3") (pinfunction "3_3") (pintype "passive"))
      (node (ref "U4") (pin "12") (pinfunction "PB14/TIO/MOSI_/PWM10_12") (pintype "bidirectional"))
    )
    (net (code "27") (name "/TXD") (class "Default")
      (node (ref "P3") (pin "5") (pinfunction "5_5") (pintype "passive"))
      (node (ref "U4") (pin "17") (pinfunction "PB7/TXD0/PWM9_17") (pintype "bidirectional"))
    )
    (net (code "28") (name "/UD_N") (class "Default")
      (node (ref "P1") (pin "A7") (pinfunction "Dn1_A7") (pintype "passive"))
      (node (ref "P1") (pin "B7") (pinfunction "Dn2_B7") (pintype "passive"))
      (node (ref "U4") (pin "14") (pinfunction "PB12/U2D-/SCS_/SDA/RXD1__14") (pintype "bidirectional"))
    )
    (net (code "29") (name "/UD_P") (class "Default")
      (node (ref "P1") (pin "A6") (pinfunction "Dp1_A6") (pintype "passive"))
      (node (ref "P1") (pin "B6") (pinfunction "Dp2_B6") (pintype "passive"))
      (node (ref "U4") (pin "13") (pinfunction "PB13/U2D+/SCK0_/SCL/TXD1__13") (pintype "bidirectional"))
    )
    (net (code "30") (name "/VINTA") (class "Default")
      (node (ref "C4") (pin "1") (pinfunction "1_1") (pintype "passive"))
      (node (ref "U4") (pin "33") (pinfunction "VINTA_33") (pintype "power_in"))
    )
    (net (code "31") (name "/VSW") (class "Default")
      (node (ref "L1") (pin "1") (pinfunction "1_1") (pintype "passive"))
      (node (ref "U4") (pin "2") (pinfunction "VSW_2") (pintype "power_in"))
    )
    (net (code "32") (name "/X32MI") (class "Default")
      (node (ref "U4") (pin "32") (pinfunction "X32MI_32") (pintype "input"))
      (node (ref "Y1") (pin "1") (pinfunction "XIN_1") (pintype "passive"))
    )
    (net (code "33") (name "/X32MO") (class "Default")
      (node (ref "U4") (pin "31") (pinfunction "X32MO_31") (pintype "output"))
      (node (ref "Y1") (pin "3") (pinfunction "XOUT_3") (pintype "passive"))
    )
    (net (code "34") (name "GND") (class "Default")
      (node (ref "C1") (pin "2") (pinfunction "2_2") (pintype "passive"))
      (node (ref "C11") (pin "1") (pinfunction "1_1") (pintype "passive"))
      (node (ref "C12") (pin "2") (pinfunction "2_2") (pintype "passive"))
      (node (ref "C15") (pin "1") (pinfunction "1_1") (pintype "passive"))
      (node (ref "C16") (pin "2") (pinfunction "2_2") (pintype "passive"))
      (node (ref "C17") (pin "1") (pinfunction "1_1") (pintype "passive"))
      (node (ref "C18") (pin "2") (pinfunction "2_2") (pintype "passive"))
      (node (ref "C2") (pin "2") (pinfunction "2_2") (pintype "passive"))
      (node (ref "C3") (pin "2") (pinfunction "2_2") (pintype "passive"))
      (node (ref "C4") (pin "2") (pinfunction "2_2") (pintype "passive"))
      (node (ref "C5") (pin "2") (pinfunction "2_2") (pintype "passive"))
      (node (ref "C6") (pin "1") (pinfunction "1_1") (pintype "passive"))
      (node (ref "C7") (pin "1") (pinfunction "1_1") (pintype "passive"))
      (node (ref "C8") (pin "2") (pinfunction "2_2") (pintype "passive"))
      (node (ref "P1") (pin "A1") (pinfunction "GND_A1") (pintype "passive"))
      (node (ref "P1") (pin "A12") (pinfunction "GND_A12") (pintype "passive"))
      (node (ref "P1") (pin "B1") (pinfunction "GND_B1") (pintype "passive"))
      (node (ref "P1") (pin "B12") (pinfunction "GND_B12") (pintype "passive"))
      (node (ref "P2") (pin "2") (pinfunction "2_2") (pintype "passive"))
      (node (ref "P3") (pin "2") (pinfunction "2_2") (pintype "passive"))
      (node (ref "R1") (pin "2") (pintype "passive"))
      (node (ref "R2") (pin "1") (pintype "passive"))
      (node (ref "R4") (pin "1") (pintype "passive"))
      (node (ref "S2") (pin "1") (pinfunction "1_1") (pintype "passive"))
      (node (ref "U1") (pin "2") (pinfunction "GND_2") (pintype "passive"))
      (node (ref "U2") (pin "1") (pinfunction "GND_1") (pintype "power_in"))
      (node (ref "U3") (pin "1") (pinfunction "GND_1") (pintype "passive"))
      (node (ref "U4") (pin "0") (pinfunction "GND_0") (pintype "power_in"))
      (node (ref "Y1") (pin "2") (pinfunction "GND_2") (pintype "passive"))
      (node (ref "Y1") (pin "4") (pinfunction "GND_4") (pintype "passive"))
    )
    (net (code "35") (name "Net-(C9-Pad2)") (class "Default")
      (node (ref "C9") (pin "2") (pinfunction "2_2") (pintype "passive"))
      (node (ref "R5") (pin "1") (pintype "passive"))
      (node (ref "R7") (pin "2") (pintype "passive"))
    )
    (net (code "36") (name "Net-(C10-Pad1)") (class "Default")
      (node (ref "C10") (pin "1") (pinfunction "1_1") (pintype "passive"))
      (node (ref "C12") (pin "1") (pinfunction "1_1") (pintype "passive"))
      (node (ref "C14") (pin "1") (pinfunction "1_1") (pintype "passive"))
      (node (ref "L3") (pin "2") (pinfunction "2_2") (pintype "passive"))
    )
    (net (code "37") (name "Net-(C10-Pad2)") (class "Default")
      (node (ref "C10") (pin "2") (pinfunction "2_2") (pintype "passive"))
      (node (ref "C11") (pin "2") (pinfunction "2_2") (pintype "passive"))
      (node (ref "C13") (pin "1") (pinfunction "1_1") (pintype "passive"))
      (node (ref "L2") (pin "2") (pinfunction "2_2") (pintype "passive"))
    )
    (net (code "38") (name "Net-(C13-Pad2)") (class "Default")
      (node (ref "C13") (pin "2") (pinfunction "2_2") (pintype "passive"))
      (node (ref "C15") (pin "2") (pinfunction "2_2") (pintype "passive"))
      (node (ref "C17") (pin "2") (pinfunction "2_2") (pintype "passive"))
      (node (ref "R7") (pin "1") (pintype "passive"))
      (node (ref "R8") (pin "1") (pintype "passive"))
    )
    (net (code "39") (name "Net-(C14-Pad2)") (class "Default")
      (node (ref "C14") (pin "2") (pinfunction "2_2") (pintype "passive"))
      (node (ref "C16") (pin "1") (pinfunction "1_1") (pintype "passive"))
      (node (ref "C18") (pin "1") (pinfunction "1_1") (pintype "passive"))
      (node (ref "R10") (pin "1") (pintype "passive"))
    )
    (net (code "40") (name "Net-(D1-A)") (class "Default")
      (node (ref "D1") (pin "1") (pinfunction "A_1") (pintype "passive"))
      (node (ref "R3") (pin "1") (pintype "passive"))
    )
    (net (code "41") (name "Net-(D1-K)") (class "Default")
      (node (ref "D1") (pin "2") (pinfunction "K_2") (pintype "passive"))
      (node (ref "U1") (pin "1") (pinfunction "#CHRG_1") (pintype "passive"))
    )
    (net (code "42") (name "Net-(D2-A)") (class "Default")
      (node (ref "D2") (pin "1") (pinfunction "A_1") (pintype "passive"))
      (node (ref "R11") (pin "2") (pintype "passive"))
    )
    (net (code "43") (name "Net-(D3-A)") (class "Default")
      (node (ref "D3") (pin "1") (pinfunction "A_1") (pintype "passive"))
      (node (ref "R12") (pin "2") (pintype "passive"))
    )
    (net (code "44") (name "Net-(P1-CC1)") (class "Default")
      (node (ref "P1") (pin "A5") (pinfunction "CC1_A5") (pintype "passive"))
      (node (ref "R1") (pin "1") (pintype "passive"))
    )
    (net (code "45") (name "Net-(P1-CC2)") (class "Default")
      (node (ref "P1") (pin "B5") (pinfunction "CC2_B5") (pintype "passive"))
      (node (ref "R2") (pin "2") (pintype "passive"))
    )
    (net (code "46") (name "Net-(R10-Pad2)") (class "Default")
      (node (ref "R10") (pin "2") (pintype "passive"))
      (node (ref "R8") (pin "2") (pintype "passive"))
    )
    (net (code "47") (name "Net-(U1-PROG)") (class "Default")
      (node (ref "R4") (pin "2") (pintype "passive"))
      (node (ref "U1") (pin "5") (pinfunction "PROG_5") (pintype "passive"))
    )
    (net (code "48") (name "Net-(U3-Vin)") (class "Default")
      (node (ref "C2") (pin "1") (pinfunction "1_1") (pintype "passive"))
      (node (ref "S1") (pin "3") (pinfunction "3_3") (pintype "passive"))
      (node (ref "U3") (pin "3") (pinfunction "Vin_3") (pintype "passive"))
    )
    (net (code "49") (name "VBAT") (class "Default")
      (node (ref "P2") (pin "1") (pinfunction "1_1") (pintype "passive"))
      (node (ref "U1") (pin "3") (pinfunction "BAT_3") (pintype "passive"))
      (node (ref "U2") (pin "3") (pinfunction "VI+_3") (pintype "power_in"))
    )
    (net (code "50") (name "VBUS") (class "Default")
      (node (ref "C1") (pin "1") (pinfunction "1_1") (pintype "passive"))
      (node (ref "P1") (pin "A4") (pinfunction "VBUS_A4") (pintype "passive"))
      (node (ref "P1") (pin "A9") (pinfunction "VBUS_A9") (pintype "passive"))
      (node (ref "P1") (pin "B4") (pinfunction "VBUS_B4") (pintype "passive"))
      (node (ref "P1") (pin "B9") (pinfunction "VBUS_B9") (pintype "passive"))
      (node (ref "R3") (pin "2") (pintype "passive"))
      (node (ref "S1") (pin "2") (pinfunction "2_2") (pintype "passive"))
      (node (ref "U1") (pin "4") (pinfunction "VCC_4") (pintype "passive"))
      (node (ref "U2") (pin "2") (pinfunction "VO-_2") (pintype "power_in"))
    )
    (net (code "51") (name "VCC") (class "Default")
      (node (ref "C3") (pin "1") (pinfunction "1_1") (pintype "passive"))
      (node (ref "C7") (pin "2") (pinfunction "2_2") (pintype "passive"))
      (node (ref "P3") (pin "1") (pinfunction "1_1") (pintype "passive"))
      (node (ref "R11") (pin "1") (pintype "passive"))
      (node (ref "R12") (pin "1") (pintype "passive"))
      (node (ref "U3") (pin "2") (pinfunction "Vout_2") (pintype "passive"))
      (node (ref "U4") (pin "3") (pinfunction "VIO33/VDD33_3") (pintype "power_in"))
    )
    (net (code "52") (name "VDCIA") (class "Default")
      (node (ref "C5") (pin "1") (pinfunction "1_1") (pintype "passive"))
      (node (ref "C6") (pin "2") (pinfunction "2_2") (pintype "passive"))
      (node (ref "L1") (pin "2") (pinfunction "2_2") (pintype "passive"))
      (node (ref "U4") (pin "1") (pinfunction "VDCID_1") (pintype "power_in"))
      (node (ref "U4") (pin "35") (pinfunction "VDCIA_35") (pintype "power_in"))
    )
    (net (code "53") (name "unconnected-(P1-SBU1-PadA8)") (class "Default")
      (node (ref "P1") (pin "A8") (pinfunction "SBU1_A8") (pintype "passive+no_connect"))
    )
    (net (code "54") (name "unconnected-(P1-SBU2-PadB8)") (class "Default")
      (node (ref "P1") (pin "B8") (pinfunction "SBU2_B8") (pintype "passive+no_connect"))
    )
    (net (code "55") (name "unconnected-(S1-Pad1)") (class "Default")
      (node (ref "S1") (pin "1") (pinfunction "1_1") (pintype "passive"))
    )
    (net (code "56") (name "unconnected-(U4-PA10{slash}X32KI{slash}TMR1-Pad48)") (class "Default")
      (node (ref "U4") (pin "48") (pinfunction "PA10/X32KI/TMR1_48") (pintype "bidirectional+no_connect"))
    )
    (net (code "57") (name "unconnected-(U4-PA11{slash}X32KO{slash}TMR2-Pad47)") (class "Default")
      (node (ref "U4") (pin "47") (pinfunction "PA11/X32KO/TMR2_47") (pintype "bidirectional+no_connect"))
    )
    (net (code "58") (name "unconnected-(U4-PB2{slash}PWM8_-Pad22)") (class "Default")
      (node (ref "U4") (pin "22") (pinfunction "PB2/PWM8__22") (pintype "bidirectional+no_connect"))
    )
    (net (code "59") (name "unconnected-(U4-PB3{slash}DCD{slash}PWM9_-Pad21)") (class "Default")
      (node (ref "U4") (pin "21") (pinfunction "PB3/DCD/PWM9__21") (pintype "bidirectional+no_connect"))
    )
    (net (code "60") (name "unconnected-(U4-PB5{slash}DTR-Pad19)") (class "Default")
      (node (ref "U4") (pin "19") (pinfunction "PB5/DTR_19") (pintype "bidirectional+no_connect"))
    )
    (net (code "61") (name "unconnected-(U4-PB6{slash}RTS{slash}PWM8-Pad18)") (class "Default")
      (node (ref "U4") (pin "18") (pinfunction "PB6/RTS/PWM8_18") (pintype "bidirectional+no_connect"))
    )
    (net (code "62") (name "unconnected-(U4-PB10{slash}UD-{slash}TMR1_-Pad16)") (class "Default")
      (node (ref "U4") (pin "16") (pinfunction "PB10/UD-/TMR1__16") (pintype "bidirectional+no_connect"))
    )
    (net (code "63") (name "unconnected-(U4-PB18-Pad30)") (class "Default")
      (node (ref "U4") (pin "30") (pinfunction "PB18_30") (pintype "bidirectional+no_connect"))
    )
    (net (code "64") (name "unconnected-(U4-PB19-Pad29)") (class "Default")
      (node (ref "U4") (pin "29") (pinfunction "PB19_29") (pintype "bidirectional+no_connect"))
    )
    (net (code "65") (name "unconnected-(U4-PB20{slash}SDA_{slash}RXD3_-Pad28)") (class "Default")
      (node (ref "U4") (pin "28") (pinfunction "PB20/SDA_/RXD3__28") (pintype "bidirectional+no_connect"))
    )
    (net (code "66") (name "unconnected-(U4-PB21{slash}SCL_{slash}TXD3_-Pad27)") (class "Default")
      (node (ref "U4") (pin "27") (pinfunction "PB21/SCL_/TXD3__27") (pintype "bidirectional+no_connect"))
    )
    (net (code "67") (name "unconnected-(U4-PB23{slash}TMR0_{slash}TXD2_{slash}PWM11-Pad25)") (class "Default")
      (node (ref "U4") (pin "25") (pinfunction "PB23/TMR0_/TXD2_/PWM11_25") (pintype "bidirectional+no_connect"))
    )
  )
)
